# modulator.net
KiCad netlist of a schematic drawn in EAGLE
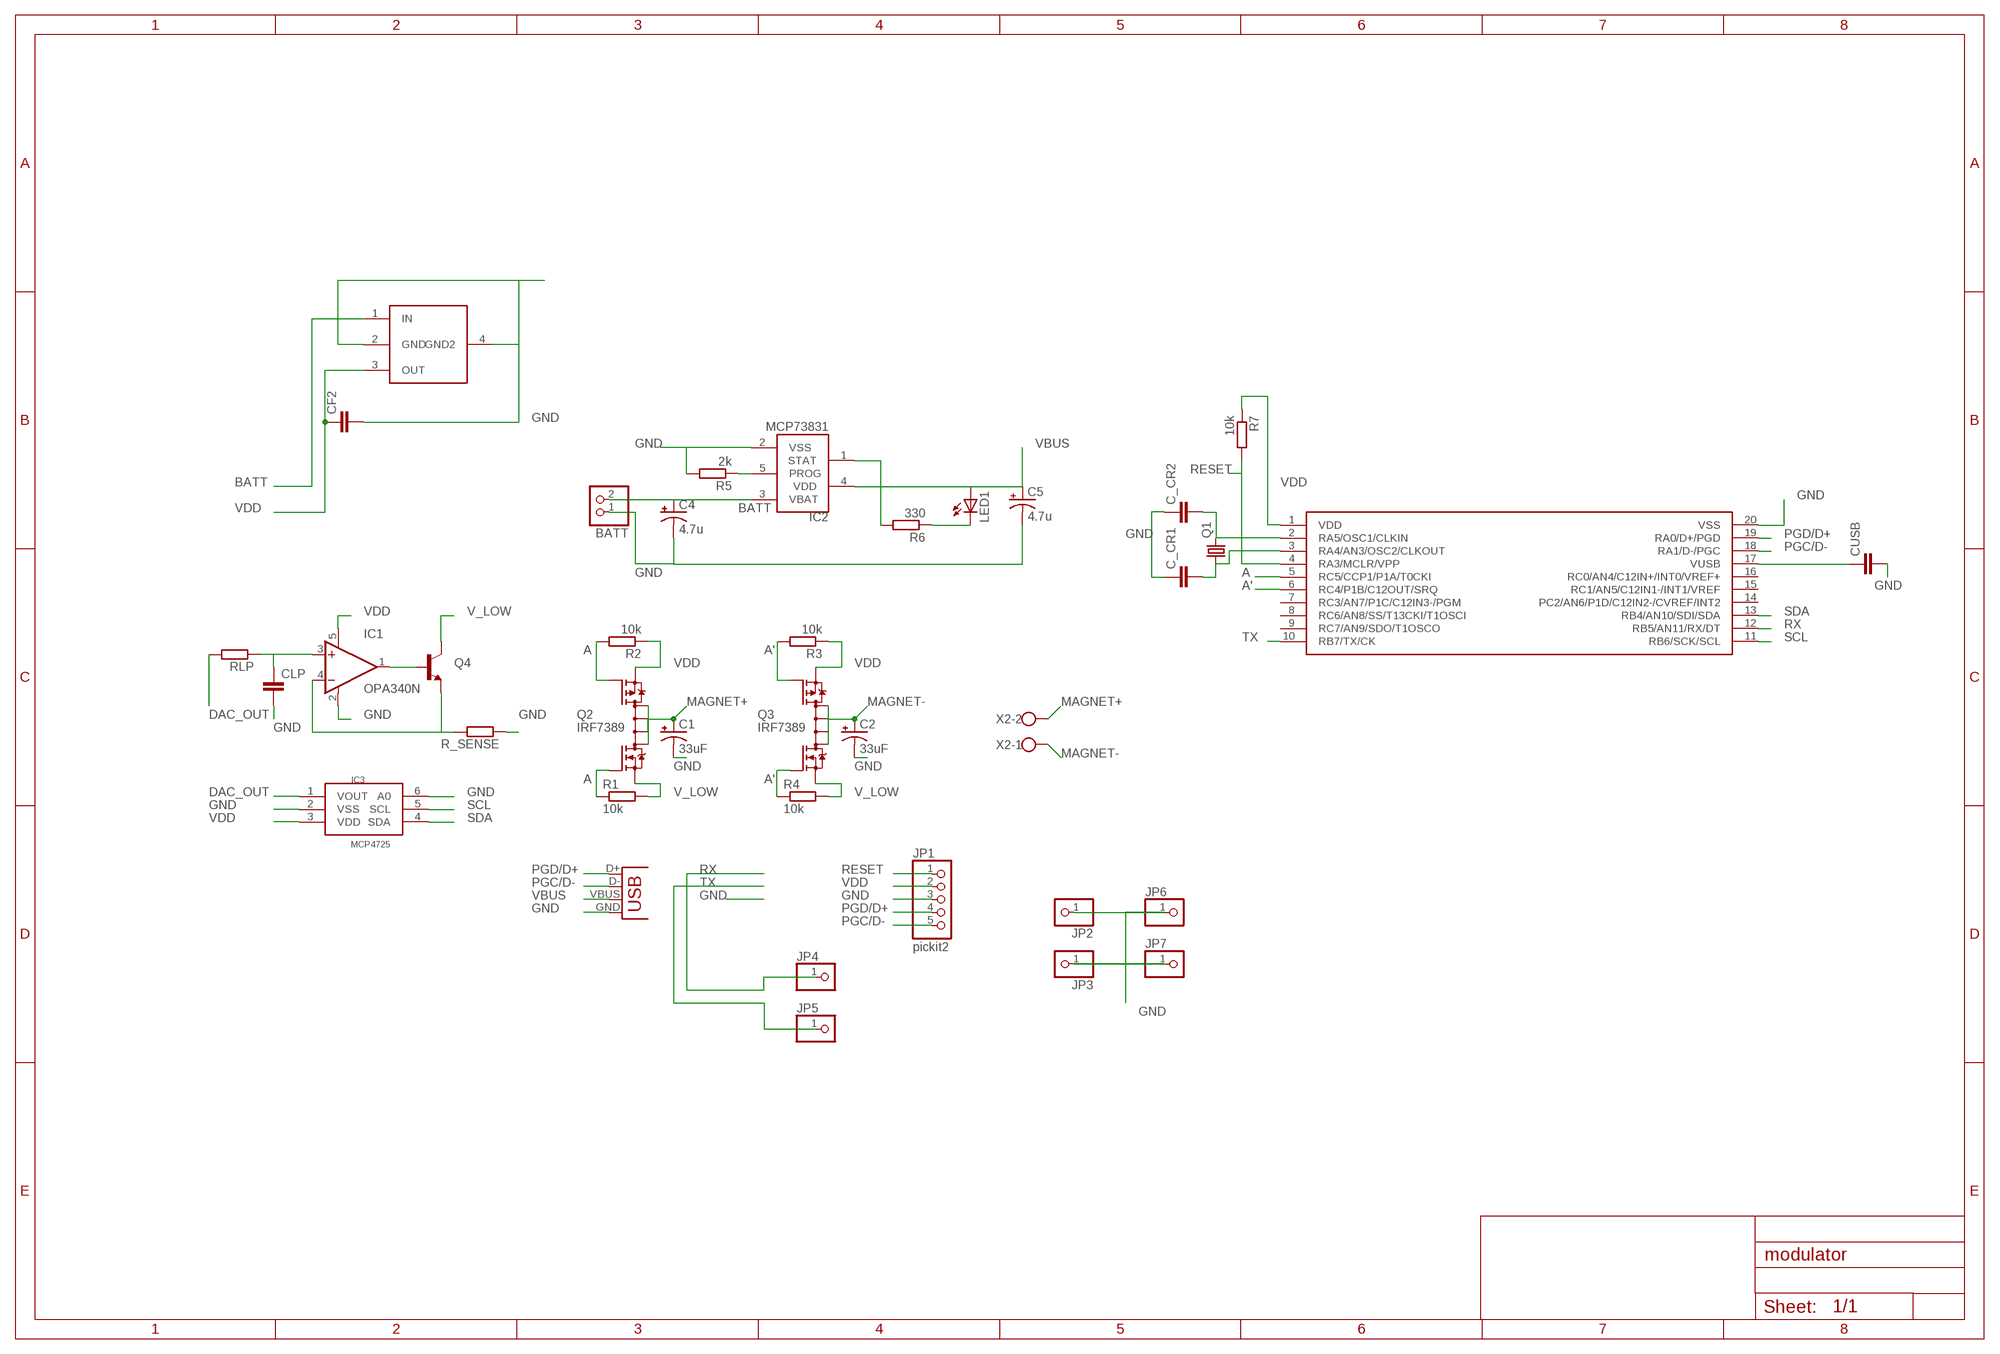
[diagram p0: schematic, sheet 1]

(export (version "E")
  (design (tool "Eeschema 10.0.6"))
  (components
    (comp (ref "BATT")
      (value "PINHD-1X2")
      (footprint "eagle-import:1X02")
      (libsource (lib "eagle-import") (part "PINHD-1X2"))
    )
    (comp (ref "C1")
      (value "33uF")
      (footprint "eagle-import:B_3528-21W")
      (libsource (lib "eagle-import") (part "CPOL-USB/3528-21W"))
    )
    (comp (ref "C2")
      (value "33uF")
      (footprint "eagle-import:B_3528-21W")
      (libsource (lib "eagle-import") (part "CPOL-USB/3528-21W"))
    )
    (comp (ref "C4")
      (value "4.7u")
      (footprint "eagle-import:B_3528-21W")
      (libsource (lib "eagle-import") (part "CPOL-USB/3528-21W"))
    )
    (comp (ref "C5")
      (value "4.7u")
      (footprint "eagle-import:B_3528-21W")
      (libsource (lib "eagle-import") (part "CPOL-USB/3528-21W"))
    )
    (comp (ref "CF2")
      (value "C-EUC1206")
      (footprint "eagle-import:C1206")
      (libsource (lib "eagle-import") (part "C-EUC1206"))
    )
    (comp (ref "CLP")
      (value "C-EUC1206")
      (footprint "eagle-import:C1206")
      (libsource (lib "eagle-import") (part "C-EUC1206"))
    )
    (comp (ref "CUSB")
      (value "C-EUC1206")
      (footprint "eagle-import:C1206")
      (libsource (lib "eagle-import") (part "C-EUC1206"))
    )
    (comp (ref "C_CR1")
      (value "C-EUC1206")
      (footprint "eagle-import:C1206")
      (libsource (lib "eagle-import") (part "C-EUC1206"))
    )
    (comp (ref "C_CR2")
      (value "C-EUC1206")
      (footprint "eagle-import:C1206")
      (libsource (lib "eagle-import") (part "C-EUC1206"))
    )
    (comp (ref "IC1")
      (value "OPA340N")
      (footprint "eagle-import:SOT23-5")
      (libsource (lib "eagle-import") (part "OPA340N"))
    )
    (comp (ref "IC2")
      (value "MCP73831")
      (footprint "eagle-import:SOT23-5L")
      (libsource (lib "eagle-import") (part "MCP73831"))
    )
    (comp (ref "IC3")
      (value "MCP4725")
      (footprint "eagle-import:SOT23-6")
      (libsource (lib "eagle-import") (part "MCP4725"))
    )
    (comp (ref "JP1")
      (value "pickit2")
      (footprint "eagle-import:1X05")
      (libsource (lib "eagle-import") (part "PINHD-1X5"))
    )
    (comp (ref "JP2")
      (value "PINHD-1X1")
      (footprint "eagle-import:1X01")
      (libsource (lib "eagle-import") (part "PINHD-1X1"))
    )
    (comp (ref "JP3")
      (value "PINHD-1X1")
      (footprint "eagle-import:1X01")
      (libsource (lib "eagle-import") (part "PINHD-1X1"))
    )
    (comp (ref "JP4")
      (value "PINHD-1X1")
      (footprint "eagle-import:1X01")
      (libsource (lib "eagle-import") (part "PINHD-1X1"))
    )
    (comp (ref "JP5")
      (value "PINHD-1X1")
      (footprint "eagle-import:1X01")
      (libsource (lib "eagle-import") (part "PINHD-1X1"))
    )
    (comp (ref "JP6")
      (value "PINHD-1X1")
      (footprint "eagle-import:1X01")
      (libsource (lib "eagle-import") (part "PINHD-1X1"))
    )
    (comp (ref "JP7")
      (value "PINHD-1X1")
      (footprint "eagle-import:1X01")
      (libsource (lib "eagle-import") (part "PINHD-1X1"))
    )
    (comp (ref "LED1")
      (value "LED1206")
      (footprint "eagle-import:LED-1206")
      (libsource (lib "eagle-import") (part "LED1206"))
    )
    (comp (ref "Q1")
      (value "CRYSTAL5X3")
      (footprint "eagle-import:CRYSTAL-SMD-5X3")
      (libsource (lib "eagle-import") (part "CRYSTAL5X3"))
    )
    (comp (ref "Q2")
      (value "IRF7389")
      (footprint "eagle-import:SO08-IRF")
      (libsource (lib "eagle-import") (part "IRF7389"))
    )
    (comp (ref "Q3")
      (value "IRF7389")
      (footprint "eagle-import:SO08-IRF")
      (libsource (lib "eagle-import") (part "IRF7389"))
    )
    (comp (ref "Q4")
      (value "TRANSISTOR_NPNSOT23")
      (footprint "eagle-import:SOT23")
      (libsource (lib "eagle-import") (part "TRANSISTOR_NPNSOT23"))
    )
    (comp (ref "R1")
      (value "10k")
      (footprint "eagle-import:R1206W")
      (libsource (lib "eagle-import") (part "R-EU_R1206W"))
    )
    (comp (ref "R2")
      (value "10k")
      (footprint "eagle-import:R1206W")
      (libsource (lib "eagle-import") (part "R-EU_R1206W"))
    )
    (comp (ref "R3")
      (value "10k")
      (footprint "eagle-import:R1206W")
      (libsource (lib "eagle-import") (part "R-EU_R1206W"))
    )
    (comp (ref "R4")
      (value "10k")
      (footprint "eagle-import:R1206W")
      (libsource (lib "eagle-import") (part "R-EU_R1206W"))
    )
    (comp (ref "R5")
      (value "2k")
      (footprint "eagle-import:R1206W")
      (libsource (lib "eagle-import") (part "R-EU_R1206W"))
    )
    (comp (ref "R6")
      (value "330")
      (footprint "eagle-import:R1206W")
      (libsource (lib "eagle-import") (part "R-EU_R1206W"))
    )
    (comp (ref "R7")
      (value "10k")
      (footprint "eagle-import:R1206W")
      (libsource (lib "eagle-import") (part "R-EU_R1206W"))
    )
    (comp (ref "RLP")
      (value "R-EU_R1206W")
      (footprint "eagle-import:R1206W")
      (libsource (lib "eagle-import") (part "R-EU_R1206W"))
    )
    (comp (ref "R_SENSE")
      (value "R-EU_R1206W")
      (footprint "eagle-import:R1206W")
      (libsource (lib "eagle-import") (part "R-EU_R1206W"))
    )
    (comp (ref "U$1")
      (value "PIC18F4X")
      (footprint "eagle-import:SSOP20")
      (libsource (lib "eagle-import") (part "PIC18F4X"))
    )
    (comp (ref "U$3")
      (value "MCP1826S")
      (footprint "eagle-import:SOT223")
      (libsource (lib "eagle-import") (part "MCP1826S"))
    )
    (comp (ref "X1")
      (value "USB-SMD-NS")
      (footprint "eagle-import:USB-MINIB-NOSTOP")
      (libsource (lib "eagle-import") (part "USB-SMD-NS"))
    )
    (comp (ref "X2")
      (value "W237-102")
      (footprint "eagle-import:W237-102")
      (libsource (lib "eagle-import") (part "W237-102"))
    )
  )
  (nets
    (net (code "1") (name "/A") (class "Default")
      (node (ref "Q2") (pin "2") (pinfunction "N-G_2") (pintype "passive"))
      (node (ref "Q2") (pin "4") (pinfunction "P-G_4") (pintype "passive"))
      (node (ref "R1") (pin "1") (pinfunction "1_1") (pintype "passive"))
      (node (ref "R2") (pin "2") (pinfunction "2_2") (pintype "passive"))
      (node (ref "U$1") (pin "5") (pinfunction "RC5/CCP1/P1A/T0CKI_5") (pintype "bidirectional"))
    )
    (net (code "2") (name "/A'") (class "Default")
      (node (ref "Q3") (pin "2") (pinfunction "N-G_2") (pintype "passive"))
      (node (ref "Q3") (pin "4") (pinfunction "P-G_4") (pintype "passive"))
      (node (ref "R3") (pin "2") (pinfunction "2_2") (pintype "passive"))
      (node (ref "R4") (pin "1") (pinfunction "1_1") (pintype "passive"))
      (node (ref "U$1") (pin "6") (pinfunction "RC4/P1B/C12OUT/SRQ_6") (pintype "bidirectional"))
    )
    (net (code "3") (name "/BATT") (class "Default")
      (node (ref "BATT") (pin "2") (pinfunction "2_2") (pintype "passive"))
      (node (ref "C4") (pin "+") (pinfunction "+_+") (pintype "passive"))
      (node (ref "IC2") (pin "3") (pinfunction "VBAT_3") (pintype "bidirectional"))
      (node (ref "U$3") (pin "1") (pinfunction "IN_1") (pintype "bidirectional"))
    )
    (net (code "4") (name "/DAC_OUT") (class "Default")
      (node (ref "IC3") (pin "1") (pinfunction "VOUT_1") (pintype "bidirectional"))
      (node (ref "RLP") (pin "2") (pinfunction "2_2") (pintype "passive"))
    )
    (net (code "5") (name "/GND") (class "Default")
      (node (ref "BATT") (pin "1") (pinfunction "1_1") (pintype "passive"))
      (node (ref "C1") (pin "-") (pinfunction "-_-") (pintype "passive"))
      (node (ref "C2") (pin "-") (pinfunction "-_-") (pintype "passive"))
      (node (ref "C4") (pin "-") (pinfunction "-_-") (pintype "passive"))
      (node (ref "C5") (pin "-") (pinfunction "-_-") (pintype "passive"))
      (node (ref "CF2") (pin "2") (pinfunction "2_2") (pintype "passive"))
      (node (ref "CLP") (pin "2") (pinfunction "2_2") (pintype "passive"))
      (node (ref "CUSB") (pin "2") (pinfunction "2_2") (pintype "passive"))
      (node (ref "C_CR1") (pin "1") (pinfunction "1_1") (pintype "passive"))
      (node (ref "C_CR2") (pin "1") (pinfunction "1_1") (pintype "passive"))
      (node (ref "IC1") (pin "2") (pinfunction "V-_2") (pintype "power_in"))
      (node (ref "IC2") (pin "2") (pinfunction "VSS_2") (pintype "bidirectional"))
      (node (ref "IC3") (pin "2") (pinfunction "VSS_2") (pintype "bidirectional"))
      (node (ref "IC3") (pin "6") (pinfunction "A0_6") (pintype "bidirectional"))
      (node (ref "JP1") (pin "3") (pinfunction "3_3") (pintype "passive"))
      (node (ref "JP2") (pin "1") (pinfunction "1_1") (pintype "passive"))
      (node (ref "JP3") (pin "1") (pinfunction "1_1") (pintype "passive"))
      (node (ref "JP6") (pin "1") (pinfunction "1_1") (pintype "passive"))
      (node (ref "JP7") (pin "1") (pinfunction "1_1") (pintype "passive"))
      (node (ref "R5") (pin "2") (pinfunction "2_2") (pintype "passive"))
      (node (ref "R_SENSE") (pin "1") (pinfunction "1_1") (pintype "passive"))
      (node (ref "U$1") (pin "20") (pinfunction "VSS_20") (pintype "bidirectional"))
      (node (ref "U$3") (pin "2") (pinfunction "GND_2") (pintype "bidirectional"))
      (node (ref "U$3") (pin "4") (pinfunction "GND2_4") (pintype "bidirectional"))
      (node (ref "X1") (pin "GND") (pinfunction "GND_GND") (pintype "bidirectional"))
    )
    (net (code "6") (name "/MAGNET+") (class "Default")
      (node (ref "C1") (pin "+") (pinfunction "+_+") (pintype "passive"))
      (node (ref "Q2") (pin "5") (pinfunction "D_5") (pintype "passive"))
      (node (ref "Q2") (pin "6") (pinfunction "D_6") (pintype "passive"))
      (node (ref "Q2") (pin "7") (pinfunction "D_7") (pintype "passive"))
      (node (ref "Q2") (pin "8") (pinfunction "D_8") (pintype "passive"))
      (node (ref "X2") (pin "2") (pinfunction "KL_2") (pintype "passive"))
    )
    (net (code "7") (name "/MAGNET-") (class "Default")
      (node (ref "C2") (pin "+") (pinfunction "+_+") (pintype "passive"))
      (node (ref "Q3") (pin "5") (pinfunction "D_5") (pintype "passive"))
      (node (ref "Q3") (pin "6") (pinfunction "D_6") (pintype "passive"))
      (node (ref "Q3") (pin "7") (pinfunction "D_7") (pintype "passive"))
      (node (ref "Q3") (pin "8") (pinfunction "D_8") (pintype "passive"))
      (node (ref "X2") (pin "1") (pinfunction "KL_1") (pintype "passive"))
    )
    (net (code "8") (name "/PGC{slash}D-") (class "Default")
      (node (ref "JP1") (pin "5") (pinfunction "5_5") (pintype "passive"))
      (node (ref "U$1") (pin "18") (pinfunction "RA1/D-/PGC_18") (pintype "bidirectional"))
      (node (ref "X1") (pin "D-") (pinfunction "D-_D-") (pintype "bidirectional"))
    )
    (net (code "9") (name "/PGD{slash}D+") (class "Default")
      (node (ref "JP1") (pin "4") (pinfunction "4_4") (pintype "passive"))
      (node (ref "U$1") (pin "19") (pinfunction "RA0/D+/PGD_19") (pintype "bidirectional"))
      (node (ref "X1") (pin "D+") (pinfunction "D+_D+") (pintype "bidirectional"))
    )
    (net (code "10") (name "/RESET") (class "Default")
      (node (ref "JP1") (pin "1") (pinfunction "1_1") (pintype "passive"))
      (node (ref "R7") (pin "2") (pinfunction "2_2") (pintype "passive"))
      (node (ref "U$1") (pin "4") (pinfunction "RA3/MCLR/VPP_4") (pintype "bidirectional"))
    )
    (net (code "11") (name "/RX") (class "Default")
      (node (ref "JP4") (pin "1") (pinfunction "1_1") (pintype "passive"))
      (node (ref "U$1") (pin "12") (pinfunction "RB5/AN11/RX/DT_12") (pintype "bidirectional"))
    )
    (net (code "12") (name "/SCL") (class "Default")
      (node (ref "IC3") (pin "5") (pinfunction "SCL_5") (pintype "bidirectional"))
      (node (ref "U$1") (pin "11") (pinfunction "RB6/SCK/SCL_11") (pintype "bidirectional"))
    )
    (net (code "13") (name "/SDA") (class "Default")
      (node (ref "IC3") (pin "4") (pinfunction "SDA_4") (pintype "bidirectional"))
      (node (ref "U$1") (pin "13") (pinfunction "RB4/AN10/SDI/SDA_13") (pintype "bidirectional"))
    )
    (net (code "14") (name "/TX") (class "Default")
      (node (ref "JP5") (pin "1") (pinfunction "1_1") (pintype "passive"))
      (node (ref "U$1") (pin "10") (pinfunction "RB7/TX/CK_10") (pintype "bidirectional"))
    )
    (net (code "15") (name "/VBUS") (class "Default")
      (node (ref "C5") (pin "+") (pinfunction "+_+") (pintype "passive"))
      (node (ref "IC2") (pin "4") (pinfunction "VDD_4") (pintype "bidirectional"))
      (node (ref "LED1") (pin "A") (pinfunction "A_A") (pintype "passive"))
      (node (ref "X1") (pin "VBUS") (pinfunction "VBUS_VBUS") (pintype "bidirectional"))
    )
    (net (code "16") (name "/VDD") (class "Default")
      (node (ref "CF2") (pin "1") (pinfunction "1_1") (pintype "passive"))
      (node (ref "IC1") (pin "5") (pinfunction "V+_5") (pintype "power_in"))
      (node (ref "IC3") (pin "3") (pinfunction "VDD_3") (pintype "bidirectional"))
      (node (ref "JP1") (pin "2") (pinfunction "2_2") (pintype "passive"))
      (node (ref "Q2") (pin "3") (pinfunction "P-S_3") (pintype "passive"))
      (node (ref "Q3") (pin "3") (pinfunction "P-S_3") (pintype "passive"))
      (node (ref "R2") (pin "1") (pinfunction "1_1") (pintype "passive"))
      (node (ref "R3") (pin "1") (pinfunction "1_1") (pintype "passive"))
      (node (ref "R7") (pin "1") (pinfunction "1_1") (pintype "passive"))
      (node (ref "U$1") (pin "1") (pinfunction "VDD_1") (pintype "bidirectional"))
      (node (ref "U$3") (pin "3") (pinfunction "OUT_3") (pintype "bidirectional"))
    )
    (net (code "17") (name "/V_LOW") (class "Default")
      (node (ref "Q2") (pin "1") (pinfunction "N-S_1") (pintype "passive"))
      (node (ref "Q3") (pin "1") (pinfunction "N-S_1") (pintype "passive"))
      (node (ref "Q4") (pin "3") (pinfunction "C_3") (pintype "passive"))
      (node (ref "R1") (pin "2") (pinfunction "2_2") (pintype "passive"))
      (node (ref "R4") (pin "2") (pinfunction "2_2") (pintype "passive"))
    )
    (net (code "18") (name "Net-(IC1-+IN)") (class "Default")
      (node (ref "CLP") (pin "1") (pinfunction "1_1") (pintype "passive"))
      (node (ref "IC1") (pin "3") (pinfunction "+IN_3") (pintype "input"))
      (node (ref "RLP") (pin "1") (pinfunction "1_1") (pintype "passive"))
    )
    (net (code "19") (name "Net-(IC1--IN)") (class "Default")
      (node (ref "IC1") (pin "4") (pinfunction "-IN_4") (pintype "input"))
      (node (ref "Q4") (pin "2") (pinfunction "E_2") (pintype "passive"))
      (node (ref "R_SENSE") (pin "2") (pinfunction "2_2") (pintype "passive"))
    )
    (net (code "20") (name "Net-(IC1-OUT)") (class "Default")
      (node (ref "IC1") (pin "1") (pinfunction "OUT_1") (pintype "output"))
      (node (ref "Q4") (pin "1") (pinfunction "B_1") (pintype "passive"))
    )
    (net (code "21") (name "Net-(IC2-PROG)") (class "Default")
      (node (ref "IC2") (pin "5") (pinfunction "PROG_5") (pintype "bidirectional"))
      (node (ref "R5") (pin "1") (pinfunction "1_1") (pintype "passive"))
    )
    (net (code "22") (name "Net-(IC2-STAT)") (class "Default")
      (node (ref "IC2") (pin "1") (pinfunction "STAT_1") (pintype "bidirectional"))
      (node (ref "R6") (pin "2") (pinfunction "2_2") (pintype "passive"))
    )
    (net (code "23") (name "Net-(LED1-PadC)") (class "Default")
      (node (ref "LED1") (pin "C") (pinfunction "C_C") (pintype "passive"))
      (node (ref "R6") (pin "1") (pinfunction "1_1") (pintype "passive"))
    )
    (net (code "24") (name "Net-(Q1-2)") (class "Default")
      (node (ref "C_CR2") (pin "2") (pinfunction "2_2") (pintype "passive"))
      (node (ref "Q1") (pin "3") (pinfunction "2_3") (pintype "passive"))
      (node (ref "U$1") (pin "2") (pinfunction "RA5/OSC1/CLKIN_2") (pintype "bidirectional"))
    )
    (net (code "25") (name "Net-(U$1-RA4{slash}AN3{slash}OSC2{slash}CLKOUT)") (class "Default")
      (node (ref "C_CR1") (pin "2") (pinfunction "2_2") (pintype "passive"))
      (node (ref "Q1") (pin "1") (pinfunction "1_1") (pintype "passive"))
      (node (ref "U$1") (pin "3") (pinfunction "RA4/AN3/OSC2/CLKOUT_3") (pintype "bidirectional"))
    )
    (net (code "26") (name "Net-(U$1-VUSB)") (class "Default")
      (node (ref "CUSB") (pin "1") (pinfunction "1_1") (pintype "passive"))
      (node (ref "U$1") (pin "17") (pinfunction "VUSB_17") (pintype "bidirectional"))
    )
    (net (code "27") (name "unconnected-(U$1-PC2{slash}AN6{slash}P1D{slash}C12IN2-{slash}CVREF{slash}INT2-Pad14)") (class "Default")
      (node (ref "U$1") (pin "14") (pinfunction "PC2/AN6/P1D/C12IN2-/CVREF/INT2_14") (pintype "bidirectional"))
    )
    (net (code "28") (name "unconnected-(U$1-RC0{slash}AN4{slash}C12IN+{slash}INT0{slash}VREF+-Pad16)") (class "Default")
      (node (ref "U$1") (pin "16") (pinfunction "RC0/AN4/C12IN+/INT0/VREF+_16") (pintype "bidirectional"))
    )
    (net (code "29") (name "unconnected-(U$1-RC1{slash}AN5{slash}C12IN1-{slash}INT1{slash}VREF-Pad15)") (class "Default")
      (node (ref "U$1") (pin "15") (pinfunction "RC1/AN5/C12IN1-/INT1/VREF_15") (pintype "bidirectional"))
    )
    (net (code "30") (name "unconnected-(U$1-RC3{slash}AN7{slash}P1C{slash}C12IN3-{slash}PGM-Pad7)") (class "Default")
      (node (ref "U$1") (pin "7") (pinfunction "RC3/AN7/P1C/C12IN3-/PGM_7") (pintype "bidirectional"))
    )
    (net (code "31") (name "unconnected-(U$1-RC6{slash}AN8{slash}SS{slash}T13CKI{slash}T1OSCI-Pad8)") (class "Default")
      (node (ref "U$1") (pin "8") (pinfunction "RC6/AN8/SS/T13CKI/T1OSCI_8") (pintype "bidirectional"))
    )
    (net (code "32") (name "unconnected-(U$1-RC7{slash}AN9{slash}SDO{slash}T1OSCO-Pad9)") (class "Default")
      (node (ref "U$1") (pin "9") (pinfunction "RC7/AN9/SDO/T1OSCO_9") (pintype "bidirectional"))
    )
  )
)
